# TBarLedWindow.net
KiCad netlist of a schematic drawn in Altium Designer
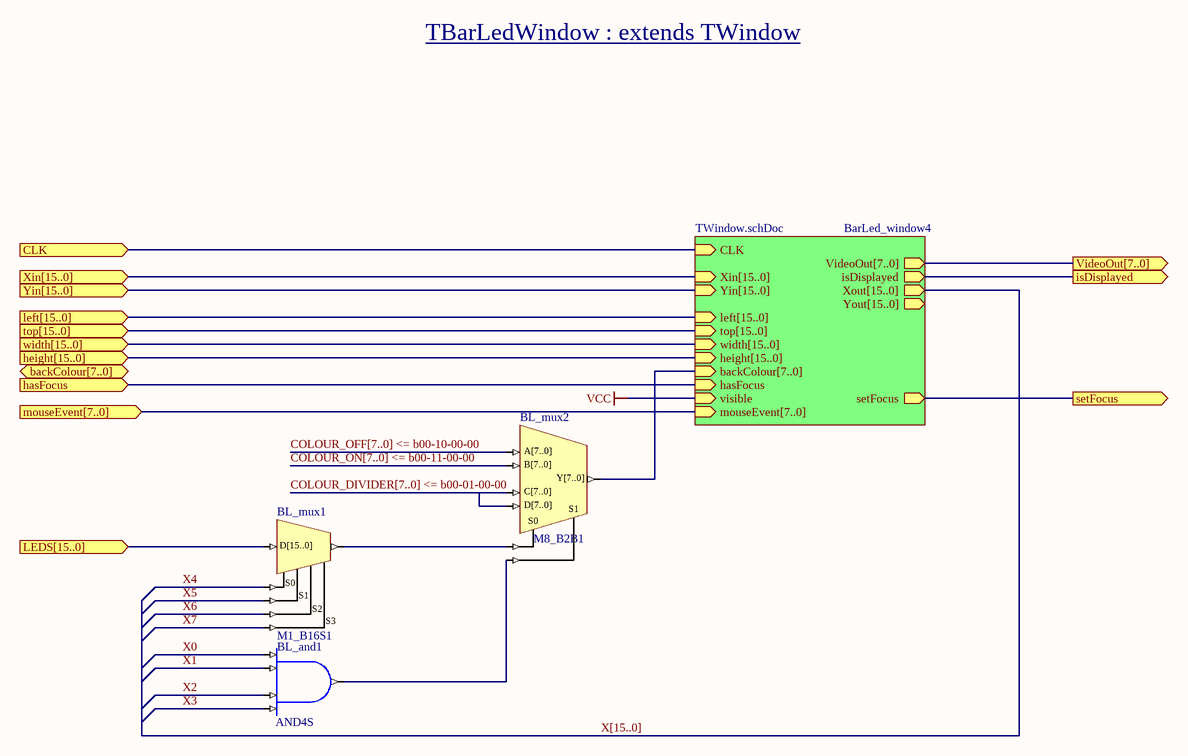
[diagram p0: TBarLedWindow.schDOC]

(export (version "E")
  (design (tool "Eeschema 10.0.6"))
  (components
    (comp (ref "BL_and1")
      (value "AND4S")
      (description "4-Input AND Gate, Single Pin Version")
      (fields (field (name "PUBLISHER") "Altium Limited"))
      (libsource (lib "FPGA Generic") (part "AND4S"))
    )
    (comp (ref "BL_mux1")
      (value "M1_B16S1")
      (description "1x16-Bit Bus to 1x1-Single Wire Multiplexer")
      (fields (field (name "PUBLISHER") "Altium Limited"))
      (libsource (lib "FPGA Generic") (part "M1_B16S1"))
    )
    (comp (ref "BL_mux2")
      (value "M8_B2B1")
      (description "4x8-Bit Bus to 1x8-Bit Bus Multiplexer")
      (fields (field (name "PUBLISHER") "Altium Limited"))
      (libsource (lib "FPGA Generic") (part "M8_B4B1"))
    )
  )
  (nets
    (net (code "146") (name "/COLOUR_DIVIDER[7..0] <= b00-01-00-00") (class "Default")
      (node (ref "BL_mux2") (pin "C[7..0]") (pinfunction "C[7..0]_C[7..0]") (pintype "input"))
    )
    (net (code "147") (name "/COLOUR_OFF[7..0] <= b00-10-00-00") (class "Default")
      (node (ref "BL_mux2") (pin "A[7..0]") (pinfunction "A[7..0]_A[7..0]") (pintype "input"))
    )
    (net (code "148") (name "/COLOUR_ON[7..0] <= b00-11-00-00") (class "Default")
      (node (ref "BL_mux2") (pin "B[7..0]") (pinfunction "B[7..0]_B[7..0]") (pintype "input"))
    )
    (net (code "149") (name "/LEDS[15..0]") (class "Default")
      (node (ref "BL_mux1") (pin "D[15..0]") (pinfunction "D[15..0]_D[15..0]") (pintype "input"))
    )
    (net (code "151") (name "/X0") (class "Default")
      (node (ref "BL_and1") (pin "I0") (pinfunction "I0_I0") (pintype "input"))
    )
    (net (code "152") (name "/X1") (class "Default")
      (node (ref "BL_and1") (pin "I1") (pinfunction "I1_I1") (pintype "input"))
    )
    (net (code "153") (name "/X2") (class "Default")
      (node (ref "BL_and1") (pin "I2") (pinfunction "I2_I2") (pintype "input"))
    )
    (net (code "154") (name "/X3") (class "Default")
      (node (ref "BL_and1") (pin "I3") (pinfunction "I3_I3") (pintype "input"))
    )
    (net (code "155") (name "/X4") (class "Default")
      (node (ref "BL_mux1") (pin "S0") (pinfunction "S0_S0") (pintype "input"))
    )
    (net (code "156") (name "/X5") (class "Default")
      (node (ref "BL_mux1") (pin "S1") (pinfunction "S1_S1") (pintype "input"))
    )
    (net (code "157") (name "/X6") (class "Default")
      (node (ref "BL_mux1") (pin "S2") (pinfunction "S2_S2") (pintype "input"))
    )
    (net (code "158") (name "/X7") (class "Default")
      (node (ref "BL_mux1") (pin "S3") (pinfunction "S3_S3") (pintype "input"))
    )
    (net (code "164") (name "/backColour[7..0]_1") (class "Default")
      (node (ref "BL_mux2") (pin "Y[7..0]") (pinfunction "Y[7..0]_Y[7..0]") (pintype "output"))
    )
    (net (code "173") (name "Net-(BL_and1-PadO)") (class "Default")
      (node (ref "BL_and1") (pin "O") (pinfunction "O_O") (pintype "output"))
      (node (ref "BL_mux2") (pin "S1") (pinfunction "S1_S1") (pintype "input"))
    )
    (net (code "174") (name "Net-(BL_mux1-PadO)") (class "Default")
      (node (ref "BL_mux1") (pin "O") (pinfunction "O_O") (pintype "output"))
      (node (ref "BL_mux2") (pin "S0") (pinfunction "S0_S0") (pintype "input"))
    )
    (net (code "176") (name "unconnected-(BL_mux2-PadD[7..0])") (class "Default")
      (node (ref "BL_mux2") (pin "D[7..0]") (pinfunction "D[7..0]_D[7..0]") (pintype "input"))
    )
  )
)
